# ProProject_circuller_2023-10-11.net
KiCad netlist of a schematic drawn in EasyEDA Pro
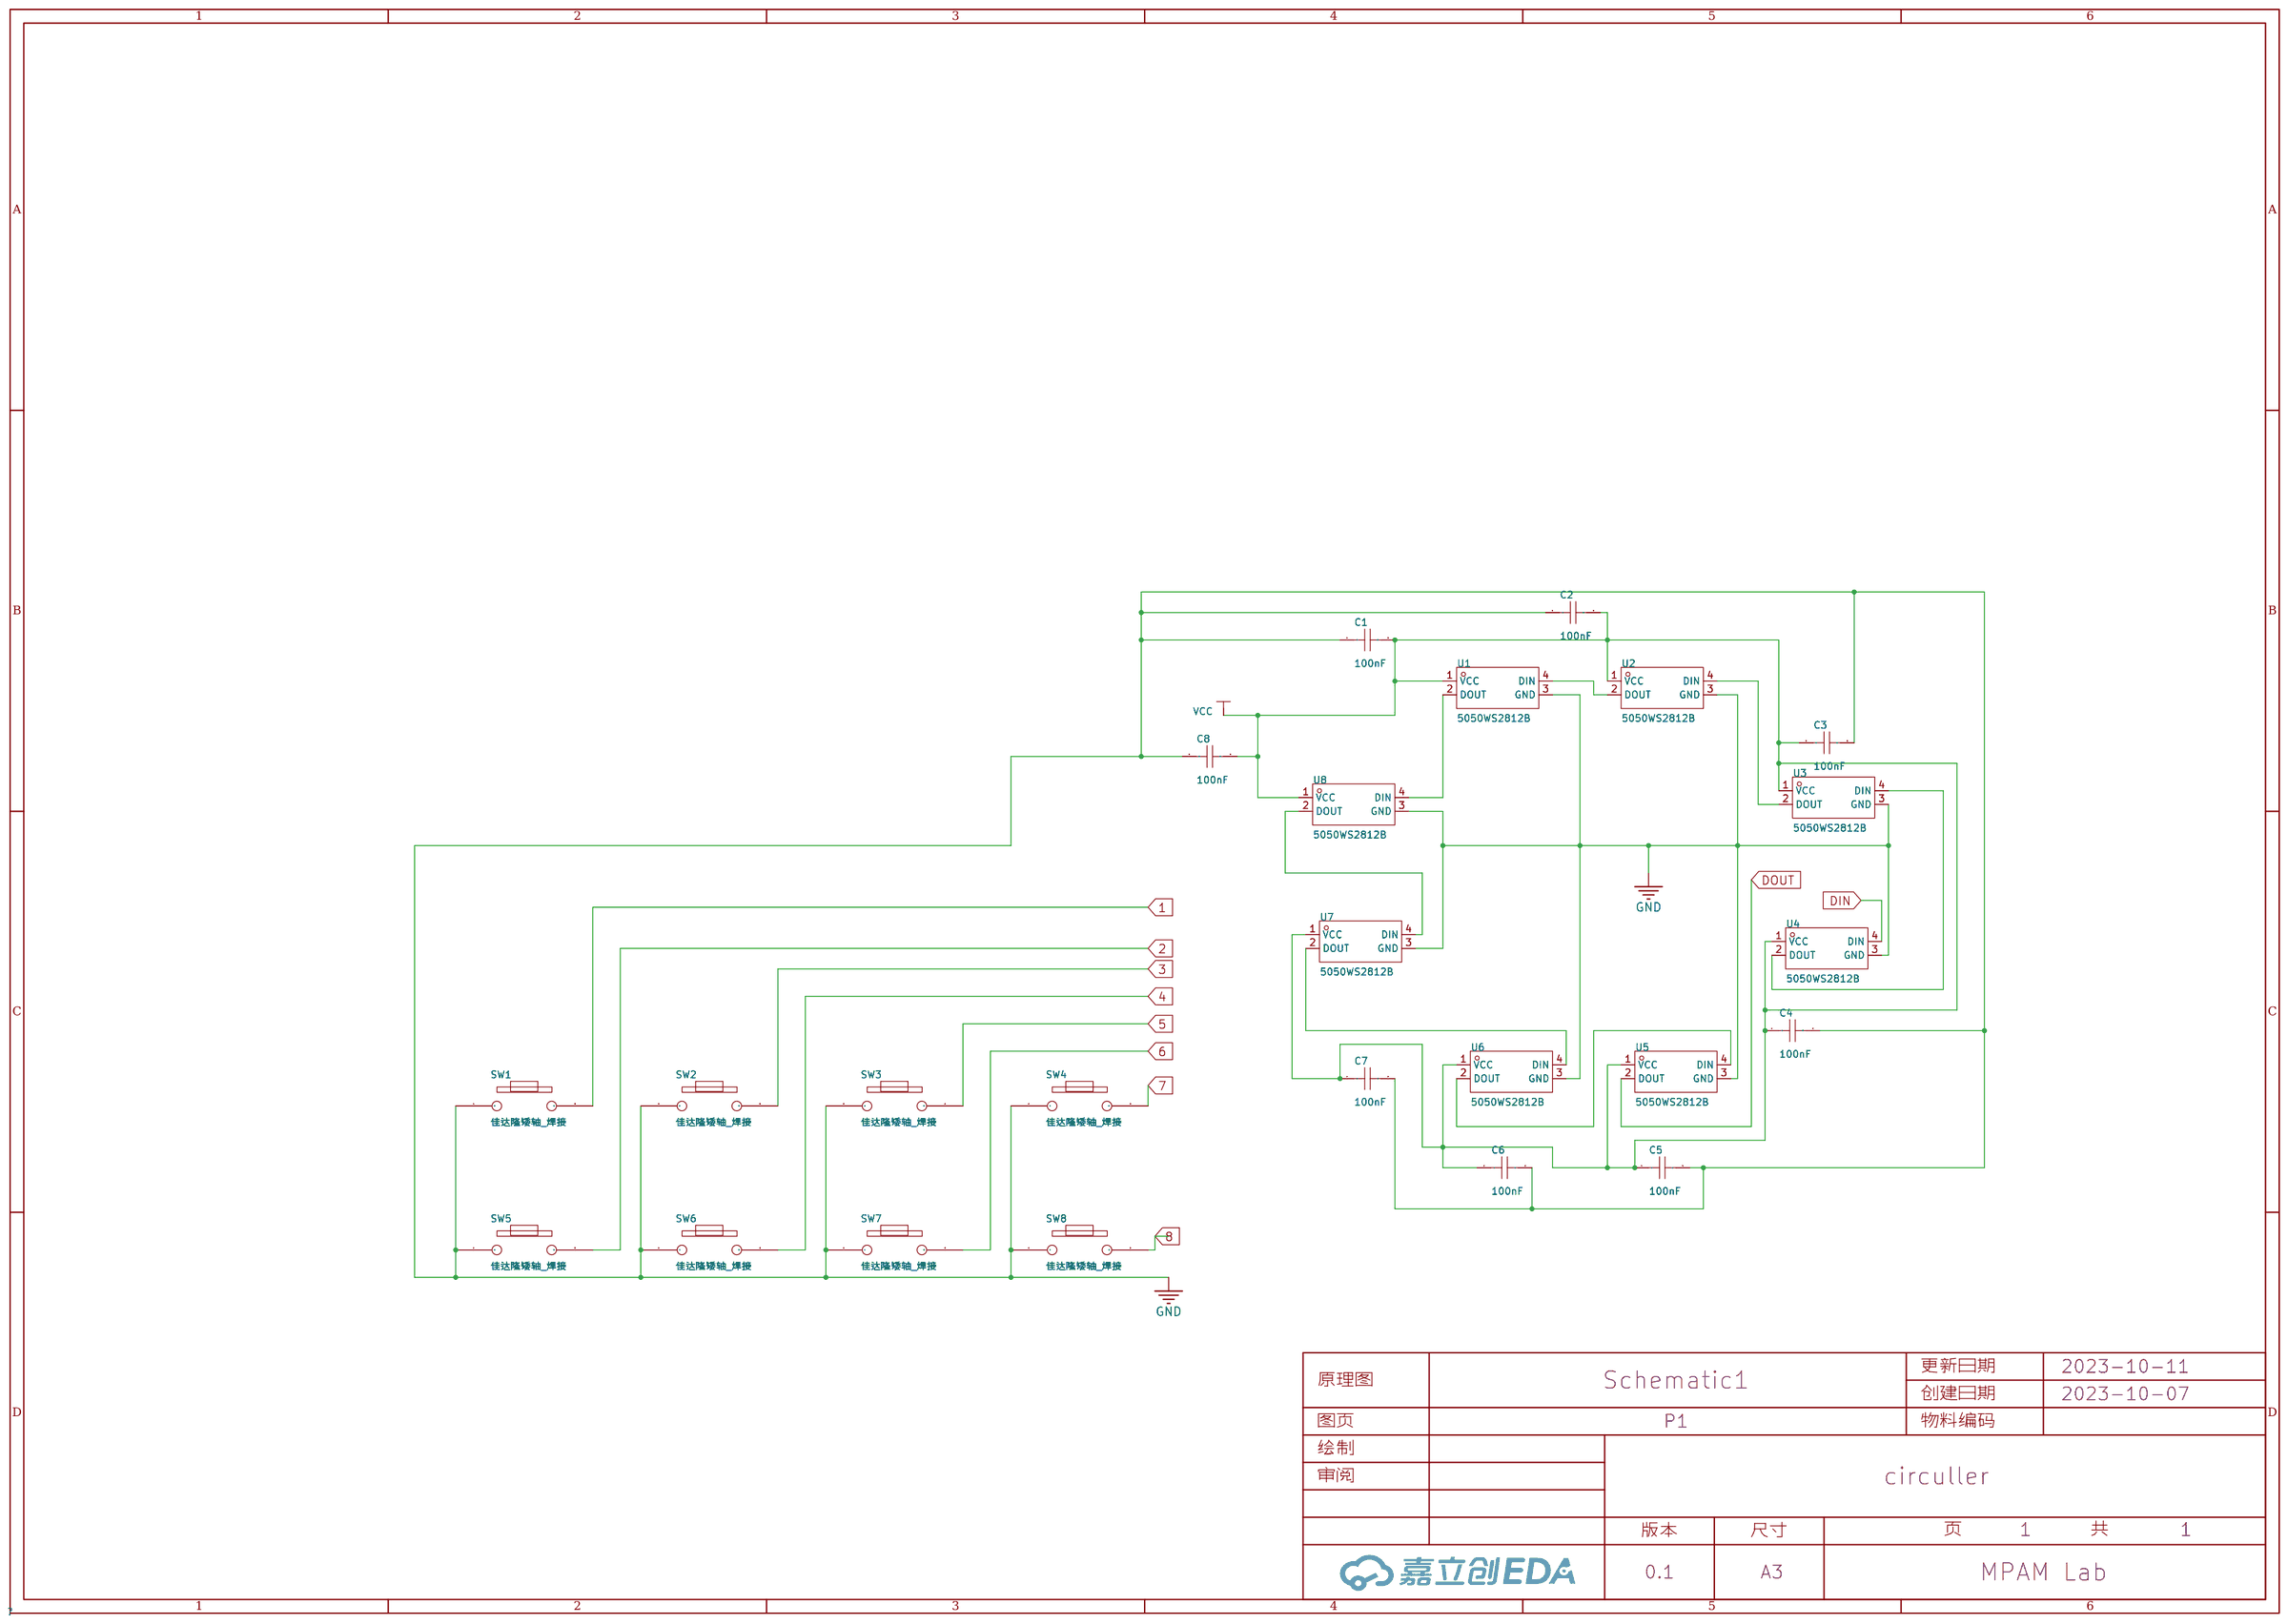
[diagram p0: schematic sheet]

(export (version "E")
  (design (tool "Eeschema 10.0.6"))
  (components
    (comp (ref "C1")
      (value "100nF")
      (footprint "easyedapro:C0603")
      (libsource (lib "easyedapro") (part "CapAcitance"))
    )
    (comp (ref "C2")
      (value "100nF")
      (footprint "easyedapro:C0603")
      (libsource (lib "easyedapro") (part "CapAcitance"))
    )
    (comp (ref "C3")
      (value "100nF")
      (footprint "easyedapro:C0603")
      (libsource (lib "easyedapro") (part "CapAcitance"))
    )
    (comp (ref "C4")
      (value "100nF")
      (footprint "easyedapro:C0603")
      (libsource (lib "easyedapro") (part "CapAcitance"))
    )
    (comp (ref "C5")
      (value "100nF")
      (footprint "easyedapro:C0603")
      (libsource (lib "easyedapro") (part "CapAcitance"))
    )
    (comp (ref "C6")
      (value "100nF")
      (footprint "easyedapro:C0603")
      (libsource (lib "easyedapro") (part "CapAcitance"))
    )
    (comp (ref "C7")
      (value "100nF")
      (footprint "easyedapro:C0603")
      (libsource (lib "easyedapro") (part "CapAcitance"))
    )
    (comp (ref "C8")
      (value "100nF")
      (footprint "easyedapro:C0603")
      (libsource (lib "easyedapro") (part "CapAcitance"))
    )
    (comp (ref "SW1") (value "佳达隆矮轴_焊接") (libsource (lib "easyedapro") (part "佳达隆矮轴_焊接")))
    (comp (ref "SW2") (value "佳达隆矮轴_焊接") (libsource (lib "easyedapro") (part "佳达隆矮轴_焊接")))
    (comp (ref "SW3") (value "佳达隆矮轴_焊接") (libsource (lib "easyedapro") (part "佳达隆矮轴_焊接")))
    (comp (ref "SW4") (value "佳达隆矮轴_焊接") (libsource (lib "easyedapro") (part "佳达隆矮轴_焊接")))
    (comp (ref "SW5") (value "佳达隆矮轴_焊接") (libsource (lib "easyedapro") (part "佳达隆矮轴_焊接")))
    (comp (ref "SW6") (value "佳达隆矮轴_焊接") (libsource (lib "easyedapro") (part "佳达隆矮轴_焊接")))
    (comp (ref "SW7") (value "佳达隆矮轴_焊接") (libsource (lib "easyedapro") (part "佳达隆矮轴_焊接")))
    (comp (ref "SW8") (value "佳达隆矮轴_焊接") (libsource (lib "easyedapro") (part "佳达隆矮轴_焊接")))
    (comp (ref "U1")
      (value "5050WS2812B")
      (footprint "easyedapro:LED-SMD_5050WS2812B")
      (libsource (lib "easyedapro") (part "5050WS2812B"))
    )
    (comp (ref "U2")
      (value "5050WS2812B")
      (footprint "easyedapro:LED-SMD_5050WS2812B")
      (libsource (lib "easyedapro") (part "5050WS2812B"))
    )
    (comp (ref "U3")
      (value "5050WS2812B")
      (footprint "easyedapro:LED-SMD_5050WS2812B")
      (libsource (lib "easyedapro") (part "5050WS2812B"))
    )
    (comp (ref "U4")
      (value "5050WS2812B")
      (footprint "easyedapro:LED-SMD_5050WS2812B")
      (libsource (lib "easyedapro") (part "5050WS2812B"))
    )
    (comp (ref "U5")
      (value "5050WS2812B")
      (footprint "easyedapro:LED-SMD_5050WS2812B")
      (libsource (lib "easyedapro") (part "5050WS2812B"))
    )
    (comp (ref "U6")
      (value "5050WS2812B")
      (footprint "easyedapro:LED-SMD_5050WS2812B")
      (libsource (lib "easyedapro") (part "5050WS2812B"))
    )
    (comp (ref "U7")
      (value "5050WS2812B")
      (footprint "easyedapro:LED-SMD_5050WS2812B")
      (libsource (lib "easyedapro") (part "5050WS2812B"))
    )
    (comp (ref "U8")
      (value "5050WS2812B")
      (footprint "easyedapro:LED-SMD_5050WS2812B")
      (libsource (lib "easyedapro") (part "5050WS2812B"))
    )
  )
  (nets
    (net (code "1") (name "1") (class "Default")
      (node (ref "SW1") (pin "2") (pinfunction "2_2") (pintype "input"))
    )
    (net (code "2") (name "2") (class "Default")
      (node (ref "SW5") (pin "2") (pinfunction "2_2") (pintype "input"))
    )
    (net (code "3") (name "3") (class "Default")
      (node (ref "SW2") (pin "2") (pinfunction "2_2") (pintype "input"))
    )
    (net (code "4") (name "4") (class "Default")
      (node (ref "SW6") (pin "2") (pinfunction "2_2") (pintype "input"))
    )
    (net (code "5") (name "5") (class "Default")
      (node (ref "SW3") (pin "2") (pinfunction "2_2") (pintype "input"))
    )
    (net (code "6") (name "6") (class "Default")
      (node (ref "SW7") (pin "2") (pinfunction "2_2") (pintype "input"))
    )
    (net (code "7") (name "7") (class "Default")
      (node (ref "SW4") (pin "2") (pinfunction "2_2") (pintype "input"))
    )
    (net (code "8") (name "8") (class "Default")
      (node (ref "SW8") (pin "2") (pinfunction "2_2") (pintype "input"))
    )
    (net (code "9") (name "DIN") (class "Default")
      (node (ref "U4") (pin "4") (pinfunction "DIN_4") (pintype "input"))
    )
    (net (code "10") (name "DOUT") (class "Default")
      (node (ref "U5") (pin "2") (pinfunction "DOUT_2") (pintype "input"))
    )
    (net (code "11") (name "GND") (class "Default")
      (node (ref "C1") (pin "1") (pinfunction "1_1") (pintype "input"))
      (node (ref "C2") (pin "1") (pinfunction "1_1") (pintype "input"))
      (node (ref "C3") (pin "2") (pinfunction "2_2") (pintype "input"))
      (node (ref "C4") (pin "2") (pinfunction "2_2") (pintype "input"))
      (node (ref "C5") (pin "2") (pinfunction "2_2") (pintype "input"))
      (node (ref "C6") (pin "2") (pinfunction "2_2") (pintype "input"))
      (node (ref "C7") (pin "2") (pinfunction "2_2") (pintype "input"))
      (node (ref "C8") (pin "1") (pinfunction "1_1") (pintype "input"))
      (node (ref "SW1") (pin "1") (pinfunction "1_1") (pintype "input"))
      (node (ref "SW2") (pin "1") (pinfunction "1_1") (pintype "input"))
      (node (ref "SW3") (pin "1") (pinfunction "1_1") (pintype "input"))
      (node (ref "SW4") (pin "1") (pinfunction "1_1") (pintype "input"))
      (node (ref "SW5") (pin "1") (pinfunction "1_1") (pintype "input"))
      (node (ref "SW6") (pin "1") (pinfunction "1_1") (pintype "input"))
      (node (ref "SW7") (pin "1") (pinfunction "1_1") (pintype "input"))
      (node (ref "SW8") (pin "1") (pinfunction "1_1") (pintype "input"))
      (node (ref "U1") (pin "3") (pinfunction "GND_3") (pintype "input"))
      (node (ref "U2") (pin "3") (pinfunction "GND_3") (pintype "input"))
      (node (ref "U3") (pin "3") (pinfunction "GND_3") (pintype "input"))
      (node (ref "U4") (pin "3") (pinfunction "GND_3") (pintype "input"))
      (node (ref "U5") (pin "3") (pinfunction "GND_3") (pintype "input"))
      (node (ref "U6") (pin "3") (pinfunction "GND_3") (pintype "input"))
      (node (ref "U7") (pin "3") (pinfunction "GND_3") (pintype "input"))
      (node (ref "U8") (pin "3") (pinfunction "GND_3") (pintype "input"))
    )
    (net (code "12") (name "Net-(U1-DIN)") (class "Default")
      (node (ref "U1") (pin "4") (pinfunction "DIN_4") (pintype "input"))
      (node (ref "U2") (pin "2") (pinfunction "DOUT_2") (pintype "input"))
    )
    (net (code "13") (name "Net-(U1-DOUT)") (class "Default")
      (node (ref "U1") (pin "2") (pinfunction "DOUT_2") (pintype "input"))
      (node (ref "U8") (pin "4") (pinfunction "DIN_4") (pintype "input"))
    )
    (net (code "14") (name "Net-(U2-DIN)") (class "Default")
      (node (ref "U2") (pin "4") (pinfunction "DIN_4") (pintype "input"))
      (node (ref "U3") (pin "2") (pinfunction "DOUT_2") (pintype "input"))
    )
    (net (code "15") (name "Net-(U3-DIN)") (class "Default")
      (node (ref "U3") (pin "4") (pinfunction "DIN_4") (pintype "input"))
      (node (ref "U4") (pin "2") (pinfunction "DOUT_2") (pintype "input"))
    )
    (net (code "16") (name "Net-(U5-DIN)") (class "Default")
      (node (ref "U5") (pin "4") (pinfunction "DIN_4") (pintype "input"))
      (node (ref "U6") (pin "2") (pinfunction "DOUT_2") (pintype "input"))
    )
    (net (code "17") (name "Net-(U6-DIN)") (class "Default")
      (node (ref "U6") (pin "4") (pinfunction "DIN_4") (pintype "input"))
      (node (ref "U7") (pin "2") (pinfunction "DOUT_2") (pintype "input"))
    )
    (net (code "18") (name "Net-(U7-DIN)") (class "Default")
      (node (ref "U7") (pin "4") (pinfunction "DIN_4") (pintype "input"))
      (node (ref "U8") (pin "2") (pinfunction "DOUT_2") (pintype "input"))
    )
    (net (code "19") (name "VCC") (class "Default")
      (node (ref "C1") (pin "2") (pinfunction "2_2") (pintype "input"))
      (node (ref "C2") (pin "2") (pinfunction "2_2") (pintype "input"))
      (node (ref "C3") (pin "1") (pinfunction "1_1") (pintype "input"))
      (node (ref "C4") (pin "1") (pinfunction "1_1") (pintype "input"))
      (node (ref "C5") (pin "1") (pinfunction "1_1") (pintype "input"))
      (node (ref "C6") (pin "1") (pinfunction "1_1") (pintype "input"))
      (node (ref "C7") (pin "1") (pinfunction "1_1") (pintype "input"))
      (node (ref "C8") (pin "2") (pinfunction "2_2") (pintype "input"))
      (node (ref "U1") (pin "1") (pinfunction "VCC_1") (pintype "input"))
      (node (ref "U2") (pin "1") (pinfunction "VCC_1") (pintype "input"))
      (node (ref "U3") (pin "1") (pinfunction "VCC_1") (pintype "input"))
      (node (ref "U4") (pin "1") (pinfunction "VCC_1") (pintype "input"))
      (node (ref "U5") (pin "1") (pinfunction "VCC_1") (pintype "input"))
      (node (ref "U6") (pin "1") (pinfunction "VCC_1") (pintype "input"))
      (node (ref "U7") (pin "1") (pinfunction "VCC_1") (pintype "input"))
      (node (ref "U8") (pin "1") (pinfunction "VCC_1") (pintype "input"))
    )
  )
)
